# 07-KSZ9031_1G_BASET_XCVR.net
KiCad netlist of a schematic drawn in Altium Designer
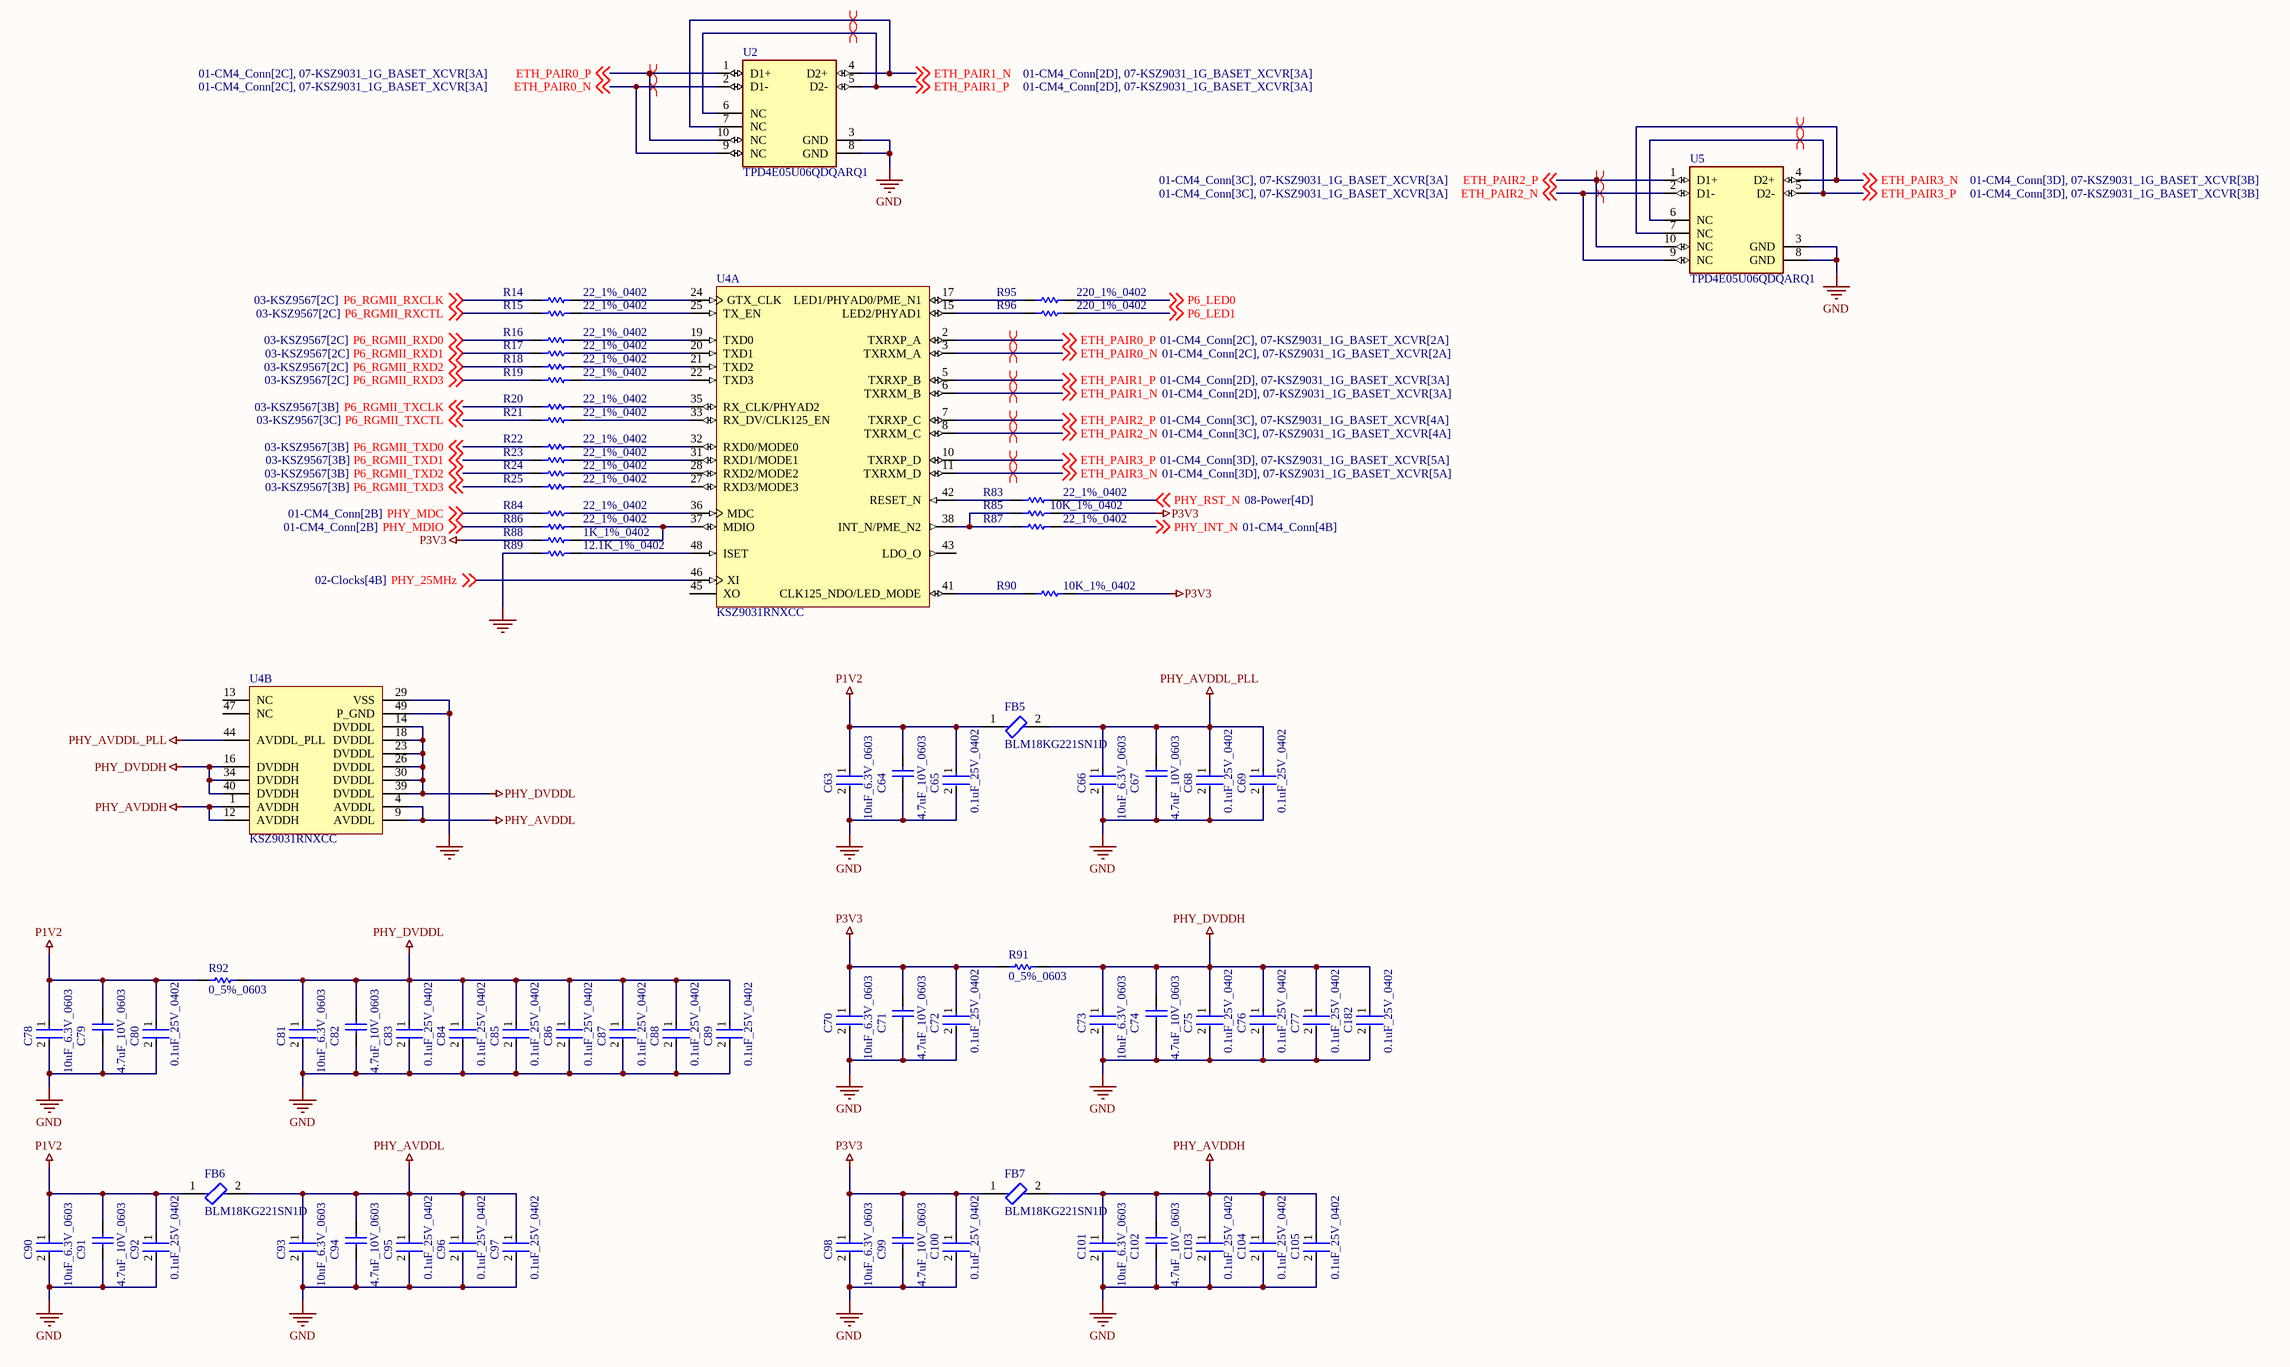
[diagram p0: 07-KSZ9031_1G_BASET_XCVR.SchDoc]

(export (version "E")
  (design (tool "Eeschema 10.0.6"))
  (components
    (comp (ref "C63")
      (value "10uF_6.3V_0603")
      (footprint "FP-C0603C106M9PACTU-MFG")
      (description "CAP CER 10UF 6.3V X5R 0603")
      (fields
        (field (name "MANUFACTURER PART NUMBER") "C0603C106M9PACTU")
        (field (name "MANUFACTURER") "Kemet")
      )
      (libsource (lib "Altium Content Vault") (part "b4654b650e69147ec39a6b967a45e02"))
    )
    (comp (ref "C64")
      (value "4.7uF_10V_0603")
      (footprint "CAPC1608X87X35NL15T15")
      (fields (field (name "PART NUMBER") "C0603C475K8PACTU") (field (name "MANUFACTURER") "Kemet"))
      (libsource (lib "Altium Content Vault") (part "CAP"))
    )
    (comp (ref "C65")
      (value "0.1uF_25V_0402")
      (footprint "FP-0402-L_1_0_1-W_0_5_0_1-IPC_C")
      (description "General Purpose Ceramic Capacitor, 0402, 100nF, 10%, X7R, 15%, 25V")
      (fields (field (name "VOLTAGE") "25V") (field (name "TOLERANCE") "10%"))
      (libsource (lib "Altium Content Vault") (part "b4654b650e69147ec39a6b967a45e02"))
    )
    (comp (ref "C66")
      (value "10uF_6.3V_0603")
      (footprint "FP-C0603C106M9PACTU-MFG")
      (description "CAP CER 10UF 6.3V X5R 0603")
      (fields
        (field (name "MANUFACTURER PART NUMBER") "C0603C106M9PACTU")
        (field (name "MANUFACTURER") "Kemet")
      )
      (libsource (lib "Altium Content Vault") (part "b4654b650e69147ec39a6b967a45e02"))
    )
    (comp (ref "C67")
      (value "4.7uF_10V_0603")
      (footprint "CAPC1608X87X35NL15T15")
      (fields (field (name "PART NUMBER") "C0603C475K8PACTU") (field (name "MANUFACTURER") "Kemet"))
      (libsource (lib "Altium Content Vault") (part "CAP"))
    )
    (comp (ref "C68")
      (value "0.1uF_25V_0402")
      (footprint "FP-0402-L_1_0_1-W_0_5_0_1-IPC_C")
      (description "General Purpose Ceramic Capacitor, 0402, 100nF, 10%, X7R, 15%, 25V")
      (fields (field (name "VOLTAGE") "25V") (field (name "TOLERANCE") "10%"))
      (libsource (lib "Altium Content Vault") (part "b4654b650e69147ec39a6b967a45e02"))
    )
    (comp (ref "C69")
      (value "0.1uF_25V_0402")
      (footprint "FP-0402-L_1_0_1-W_0_5_0_1-IPC_C")
      (description "General Purpose Ceramic Capacitor, 0402, 100nF, 10%, X7R, 15%, 25V")
      (fields (field (name "VOLTAGE") "25V") (field (name "TOLERANCE") "10%"))
      (libsource (lib "Altium Content Vault") (part "b4654b650e69147ec39a6b967a45e02"))
    )
    (comp (ref "C70")
      (value "10uF_6.3V_0603")
      (footprint "FP-C0603C106M9PACTU-MFG")
      (description "CAP CER 10UF 6.3V X5R 0603")
      (fields
        (field (name "MANUFACTURER PART NUMBER") "C0603C106M9PACTU")
        (field (name "MANUFACTURER") "Kemet")
      )
      (libsource (lib "Altium Content Vault") (part "b4654b650e69147ec39a6b967a45e02"))
    )
    (comp (ref "C71")
      (value "4.7uF_10V_0603")
      (footprint "CAPC1608X87X35NL15T15")
      (fields (field (name "PART NUMBER") "C0603C475K8PACTU") (field (name "MANUFACTURER") "Kemet"))
      (libsource (lib "Altium Content Vault") (part "CAP"))
    )
    (comp (ref "C72")
      (value "0.1uF_25V_0402")
      (footprint "FP-0402-L_1_0_1-W_0_5_0_1-IPC_C")
      (description "General Purpose Ceramic Capacitor, 0402, 100nF, 10%, X7R, 15%, 25V")
      (fields (field (name "VOLTAGE") "25V") (field (name "TOLERANCE") "10%"))
      (libsource (lib "Altium Content Vault") (part "b4654b650e69147ec39a6b967a45e02"))
    )
    (comp (ref "C73")
      (value "10uF_6.3V_0603")
      (footprint "FP-C0603C106M9PACTU-MFG")
      (description "CAP CER 10UF 6.3V X5R 0603")
      (fields
        (field (name "MANUFACTURER PART NUMBER") "C0603C106M9PACTU")
        (field (name "MANUFACTURER") "Kemet")
      )
      (libsource (lib "Altium Content Vault") (part "b4654b650e69147ec39a6b967a45e02"))
    )
    (comp (ref "C74")
      (value "4.7uF_10V_0603")
      (footprint "CAPC1608X87X35NL15T15")
      (fields (field (name "PART NUMBER") "C0603C475K8PACTU") (field (name "MANUFACTURER") "Kemet"))
      (libsource (lib "Altium Content Vault") (part "CAP"))
    )
    (comp (ref "C75")
      (value "0.1uF_25V_0402")
      (footprint "FP-0402-L_1_0_1-W_0_5_0_1-IPC_C")
      (description "General Purpose Ceramic Capacitor, 0402, 100nF, 10%, X7R, 15%, 25V")
      (fields (field (name "VOLTAGE") "25V") (field (name "TOLERANCE") "10%"))
      (libsource (lib "Altium Content Vault") (part "b4654b650e69147ec39a6b967a45e02"))
    )
    (comp (ref "C76")
      (value "0.1uF_25V_0402")
      (footprint "FP-0402-L_1_0_1-W_0_5_0_1-IPC_C")
      (description "General Purpose Ceramic Capacitor, 0402, 100nF, 10%, X7R, 15%, 25V")
      (fields (field (name "VOLTAGE") "25V") (field (name "TOLERANCE") "10%"))
      (libsource (lib "Altium Content Vault") (part "b4654b650e69147ec39a6b967a45e02"))
    )
    (comp (ref "C77")
      (value "0.1uF_25V_0402")
      (footprint "FP-0402-L_1_0_1-W_0_5_0_1-IPC_C")
      (description "General Purpose Ceramic Capacitor, 0402, 100nF, 10%, X7R, 15%, 25V")
      (fields (field (name "VOLTAGE") "25V") (field (name "TOLERANCE") "10%"))
      (libsource (lib "Altium Content Vault") (part "b4654b650e69147ec39a6b967a45e02"))
    )
    (comp (ref "C78")
      (value "10uF_6.3V_0603")
      (footprint "FP-C0603C106M9PACTU-MFG")
      (description "CAP CER 10UF 6.3V X5R 0603")
      (fields
        (field (name "MANUFACTURER PART NUMBER") "C0603C106M9PACTU")
        (field (name "MANUFACTURER") "Kemet")
      )
      (libsource (lib "Altium Content Vault") (part "b4654b650e69147ec39a6b967a45e02"))
    )
    (comp (ref "C79")
      (value "4.7uF_10V_0603")
      (footprint "CAPC1608X87X35NL15T15")
      (fields (field (name "PART NUMBER") "C0603C475K8PACTU") (field (name "MANUFACTURER") "Kemet"))
      (libsource (lib "Altium Content Vault") (part "CAP"))
    )
    (comp (ref "C80")
      (value "0.1uF_25V_0402")
      (footprint "FP-0402-L_1_0_1-W_0_5_0_1-IPC_C")
      (description "General Purpose Ceramic Capacitor, 0402, 100nF, 10%, X7R, 15%, 25V")
      (fields (field (name "VOLTAGE") "25V") (field (name "TOLERANCE") "10%"))
      (libsource (lib "Altium Content Vault") (part "b4654b650e69147ec39a6b967a45e02"))
    )
    (comp (ref "C81")
      (value "10uF_6.3V_0603")
      (footprint "FP-C0603C106M9PACTU-MFG")
      (description "CAP CER 10UF 6.3V X5R 0603")
      (fields
        (field (name "MANUFACTURER PART NUMBER") "C0603C106M9PACTU")
        (field (name "MANUFACTURER") "Kemet")
      )
      (libsource (lib "Altium Content Vault") (part "b4654b650e69147ec39a6b967a45e02"))
    )
    (comp (ref "C82")
      (value "4.7uF_10V_0603")
      (footprint "CAPC1608X87X35NL15T15")
      (fields (field (name "PART NUMBER") "C0603C475K8PACTU") (field (name "MANUFACTURER") "Kemet"))
      (libsource (lib "Altium Content Vault") (part "CAP"))
    )
    (comp (ref "C83")
      (value "0.1uF_25V_0402")
      (footprint "FP-0402-L_1_0_1-W_0_5_0_1-IPC_C")
      (description "General Purpose Ceramic Capacitor, 0402, 100nF, 10%, X7R, 15%, 25V")
      (fields (field (name "VOLTAGE") "25V") (field (name "TOLERANCE") "10%"))
      (libsource (lib "Altium Content Vault") (part "b4654b650e69147ec39a6b967a45e02"))
    )
    (comp (ref "C84")
      (value "0.1uF_25V_0402")
      (footprint "FP-0402-L_1_0_1-W_0_5_0_1-IPC_C")
      (description "General Purpose Ceramic Capacitor, 0402, 100nF, 10%, X7R, 15%, 25V")
      (fields (field (name "VOLTAGE") "25V") (field (name "TOLERANCE") "10%"))
      (libsource (lib "Altium Content Vault") (part "b4654b650e69147ec39a6b967a45e02"))
    )
    (comp (ref "C85")
      (value "0.1uF_25V_0402")
      (footprint "FP-0402-L_1_0_1-W_0_5_0_1-IPC_C")
      (description "General Purpose Ceramic Capacitor, 0402, 100nF, 10%, X7R, 15%, 25V")
      (fields (field (name "VOLTAGE") "25V") (field (name "TOLERANCE") "10%"))
      (libsource (lib "Altium Content Vault") (part "b4654b650e69147ec39a6b967a45e02"))
    )
    (comp (ref "C86")
      (value "0.1uF_25V_0402")
      (footprint "FP-0402-L_1_0_1-W_0_5_0_1-IPC_C")
      (description "General Purpose Ceramic Capacitor, 0402, 100nF, 10%, X7R, 15%, 25V")
      (fields (field (name "VOLTAGE") "25V") (field (name "TOLERANCE") "10%"))
      (libsource (lib "Altium Content Vault") (part "b4654b650e69147ec39a6b967a45e02"))
    )
    (comp (ref "C87")
      (value "0.1uF_25V_0402")
      (footprint "FP-0402-L_1_0_1-W_0_5_0_1-IPC_C")
      (description "General Purpose Ceramic Capacitor, 0402, 100nF, 10%, X7R, 15%, 25V")
      (fields (field (name "VOLTAGE") "25V") (field (name "TOLERANCE") "10%"))
      (libsource (lib "Altium Content Vault") (part "b4654b650e69147ec39a6b967a45e02"))
    )
    (comp (ref "C88")
      (value "0.1uF_25V_0402")
      (footprint "FP-0402-L_1_0_1-W_0_5_0_1-IPC_C")
      (description "General Purpose Ceramic Capacitor, 0402, 100nF, 10%, X7R, 15%, 25V")
      (fields (field (name "VOLTAGE") "25V") (field (name "TOLERANCE") "10%"))
      (libsource (lib "Altium Content Vault") (part "b4654b650e69147ec39a6b967a45e02"))
    )
    (comp (ref "C89")
      (value "0.1uF_25V_0402")
      (footprint "FP-0402-L_1_0_1-W_0_5_0_1-IPC_C")
      (description "General Purpose Ceramic Capacitor, 0402, 100nF, 10%, X7R, 15%, 25V")
      (fields (field (name "VOLTAGE") "25V") (field (name "TOLERANCE") "10%"))
      (libsource (lib "Altium Content Vault") (part "b4654b650e69147ec39a6b967a45e02"))
    )
    (comp (ref "C90")
      (value "10uF_6.3V_0603")
      (footprint "FP-C0603C106M9PACTU-MFG")
      (description "CAP CER 10UF 6.3V X5R 0603")
      (fields
        (field (name "MANUFACTURER PART NUMBER") "C0603C106M9PACTU")
        (field (name "MANUFACTURER") "Kemet")
      )
      (libsource (lib "Altium Content Vault") (part "b4654b650e69147ec39a6b967a45e02"))
    )
    (comp (ref "C91")
      (value "4.7uF_10V_0603")
      (footprint "CAPC1608X87X35NL15T15")
      (fields (field (name "PART NUMBER") "C0603C475K8PACTU") (field (name "MANUFACTURER") "Kemet"))
      (libsource (lib "Altium Content Vault") (part "CAP"))
    )
    (comp (ref "C92")
      (value "0.1uF_25V_0402")
      (footprint "FP-0402-L_1_0_1-W_0_5_0_1-IPC_C")
      (description "General Purpose Ceramic Capacitor, 0402, 100nF, 10%, X7R, 15%, 25V")
      (fields (field (name "VOLTAGE") "25V") (field (name "TOLERANCE") "10%"))
      (libsource (lib "Altium Content Vault") (part "b4654b650e69147ec39a6b967a45e02"))
    )
    (comp (ref "C93")
      (value "10uF_6.3V_0603")
      (footprint "FP-C0603C106M9PACTU-MFG")
      (description "CAP CER 10UF 6.3V X5R 0603")
      (fields
        (field (name "MANUFACTURER PART NUMBER") "C0603C106M9PACTU")
        (field (name "MANUFACTURER") "Kemet")
      )
      (libsource (lib "Altium Content Vault") (part "b4654b650e69147ec39a6b967a45e02"))
    )
    (comp (ref "C94")
      (value "4.7uF_10V_0603")
      (footprint "CAPC1608X87X35NL15T15")
      (fields (field (name "PART NUMBER") "C0603C475K8PACTU") (field (name "MANUFACTURER") "Kemet"))
      (libsource (lib "Altium Content Vault") (part "CAP"))
    )
    (comp (ref "C95")
      (value "0.1uF_25V_0402")
      (footprint "FP-0402-L_1_0_1-W_0_5_0_1-IPC_C")
      (description "General Purpose Ceramic Capacitor, 0402, 100nF, 10%, X7R, 15%, 25V")
      (fields (field (name "VOLTAGE") "25V") (field (name "TOLERANCE") "10%"))
      (libsource (lib "Altium Content Vault") (part "b4654b650e69147ec39a6b967a45e02"))
    )
    (comp (ref "C96")
      (value "0.1uF_25V_0402")
      (footprint "FP-0402-L_1_0_1-W_0_5_0_1-IPC_C")
      (description "General Purpose Ceramic Capacitor, 0402, 100nF, 10%, X7R, 15%, 25V")
      (fields (field (name "VOLTAGE") "25V") (field (name "TOLERANCE") "10%"))
      (libsource (lib "Altium Content Vault") (part "b4654b650e69147ec39a6b967a45e02"))
    )
    (comp (ref "C97")
      (value "0.1uF_25V_0402")
      (footprint "FP-0402-L_1_0_1-W_0_5_0_1-IPC_C")
      (description "General Purpose Ceramic Capacitor, 0402, 100nF, 10%, X7R, 15%, 25V")
      (fields (field (name "VOLTAGE") "25V") (field (name "TOLERANCE") "10%"))
      (libsource (lib "Altium Content Vault") (part "b4654b650e69147ec39a6b967a45e02"))
    )
    (comp (ref "C98")
      (value "10uF_6.3V_0603")
      (footprint "FP-C0603C106M9PACTU-MFG")
      (description "CAP CER 10UF 6.3V X5R 0603")
      (fields
        (field (name "MANUFACTURER PART NUMBER") "C0603C106M9PACTU")
        (field (name "MANUFACTURER") "Kemet")
      )
      (libsource (lib "Altium Content Vault") (part "b4654b650e69147ec39a6b967a45e02"))
    )
    (comp (ref "C99")
      (value "4.7uF_10V_0603")
      (footprint "CAPC1608X87X35NL15T15")
      (fields (field (name "PART NUMBER") "C0603C475K8PACTU") (field (name "MANUFACTURER") "Kemet"))
      (libsource (lib "Altium Content Vault") (part "CAP"))
    )
    (comp (ref "C100")
      (value "0.1uF_25V_0402")
      (footprint "FP-0402-L_1_0_1-W_0_5_0_1-IPC_C")
      (description "General Purpose Ceramic Capacitor, 0402, 100nF, 10%, X7R, 15%, 25V")
      (fields (field (name "VOLTAGE") "25V") (field (name "TOLERANCE") "10%"))
      (libsource (lib "Altium Content Vault") (part "b4654b650e69147ec39a6b967a45e02"))
    )
    (comp (ref "C101")
      (value "10uF_6.3V_0603")
      (footprint "FP-C0603C106M9PACTU-MFG")
      (description "CAP CER 10UF 6.3V X5R 0603")
      (fields
        (field (name "MANUFACTURER PART NUMBER") "C0603C106M9PACTU")
        (field (name "MANUFACTURER") "Kemet")
      )
      (libsource (lib "Altium Content Vault") (part "b4654b650e69147ec39a6b967a45e02"))
    )
    (comp (ref "C102")
      (value "4.7uF_10V_0603")
      (footprint "CAPC1608X87X35NL15T15")
      (fields (field (name "PART NUMBER") "C0603C475K8PACTU") (field (name "MANUFACTURER") "Kemet"))
      (libsource (lib "Altium Content Vault") (part "CAP"))
    )
    (comp (ref "C103")
      (value "0.1uF_25V_0402")
      (footprint "FP-0402-L_1_0_1-W_0_5_0_1-IPC_C")
      (description "General Purpose Ceramic Capacitor, 0402, 100nF, 10%, X7R, 15%, 25V")
      (fields (field (name "VOLTAGE") "25V") (field (name "TOLERANCE") "10%"))
      (libsource (lib "Altium Content Vault") (part "b4654b650e69147ec39a6b967a45e02"))
    )
    (comp (ref "C104")
      (value "0.1uF_25V_0402")
      (footprint "FP-0402-L_1_0_1-W_0_5_0_1-IPC_C")
      (description "General Purpose Ceramic Capacitor, 0402, 100nF, 10%, X7R, 15%, 25V")
      (fields (field (name "VOLTAGE") "25V") (field (name "TOLERANCE") "10%"))
      (libsource (lib "Altium Content Vault") (part "b4654b650e69147ec39a6b967a45e02"))
    )
    (comp (ref "C105")
      (value "0.1uF_25V_0402")
      (footprint "FP-0402-L_1_0_1-W_0_5_0_1-IPC_C")
      (description "General Purpose Ceramic Capacitor, 0402, 100nF, 10%, X7R, 15%, 25V")
      (fields (field (name "VOLTAGE") "25V") (field (name "TOLERANCE") "10%"))
      (libsource (lib "Altium Content Vault") (part "b4654b650e69147ec39a6b967a45e02"))
    )
    (comp (ref "C182")
      (value "0.1uF_25V_0402")
      (footprint "FP-0402-L_1_0_1-W_0_5_0_1-IPC_C")
      (description "General Purpose Ceramic Capacitor, 0402, 100nF, 10%, X7R, 15%, 25V")
      (fields (field (name "VOLTAGE") "25V") (field (name "TOLERANCE") "10%"))
      (libsource (lib "Altium Content Vault") (part "b4654b650e69147ec39a6b967a45e02"))
    )
    (comp (ref "FB5")
      (value "BLM18KG221SN1D")
      (footprint "FP-BLM18-0_15-t0_8-IPC_B")
      (description "Chip Ferrite Bead, 0603, 220Ω @ 100MHz, 0.05Ω, 25%, 2.2A")
      (fields (field (name "TOLERANCE") "25%"))
      (libsource (lib "Altium Content Vault") (part "5f30dd21d616792df468990f7003faa"))
    )
    (comp (ref "FB6")
      (value "BLM18KG221SN1D")
      (footprint "FP-BLM18-0_15-t0_8-IPC_B")
      (description "Chip Ferrite Bead, 0603, 220Ω @ 100MHz, 0.05Ω, 25%, 2.2A")
      (fields (field (name "TOLERANCE") "25%"))
      (libsource (lib "Altium Content Vault") (part "5f30dd21d616792df468990f7003faa"))
    )
    (comp (ref "FB7")
      (value "BLM18KG221SN1D")
      (footprint "FP-BLM18-0_15-t0_8-IPC_B")
      (description "Chip Ferrite Bead, 0603, 220Ω @ 100MHz, 0.05Ω, 25%, 2.2A")
      (fields (field (name "TOLERANCE") "25%"))
      (libsource (lib "Altium Content Vault") (part "5f30dd21d616792df468990f7003faa"))
    )
    (comp (ref "R14")
      (value "22_1%_0402")
      (footprint "RESC1005X40X25ML05T10")
      (fields (field (name "PART NUMBER") "RC0402FR-1322RL") (field (name "MANUFACTURER") "Yageo / Phycomp"))
      (libsource (lib "Altium Content Vault") (part "RES"))
    )
    (comp (ref "R15")
      (value "22_1%_0402")
      (footprint "RESC1005X40X25ML05T10")
      (fields (field (name "PART NUMBER") "RC0402FR-1322RL") (field (name "MANUFACTURER") "Yageo / Phycomp"))
      (libsource (lib "Altium Content Vault") (part "RES"))
    )
    (comp (ref "R16")
      (value "22_1%_0402")
      (footprint "RESC1005X40X25ML05T10")
      (fields (field (name "PART NUMBER") "RC0402FR-1322RL") (field (name "MANUFACTURER") "Yageo / Phycomp"))
      (libsource (lib "Altium Content Vault") (part "RES"))
    )
    (comp (ref "R17")
      (value "22_1%_0402")
      (footprint "RESC1005X40X25ML05T10")
      (fields (field (name "PART NUMBER") "RC0402FR-1322RL") (field (name "MANUFACTURER") "Yageo / Phycomp"))
      (libsource (lib "Altium Content Vault") (part "RES"))
    )
    (comp (ref "R18")
      (value "22_1%_0402")
      (footprint "RESC1005X40X25ML05T10")
      (fields (field (name "PART NUMBER") "RC0402FR-1322RL") (field (name "MANUFACTURER") "Yageo / Phycomp"))
      (libsource (lib "Altium Content Vault") (part "RES"))
    )
    (comp (ref "R19")
      (value "22_1%_0402")
      (footprint "RESC1005X40X25ML05T10")
      (fields (field (name "PART NUMBER") "RC0402FR-1322RL") (field (name "MANUFACTURER") "Yageo / Phycomp"))
      (libsource (lib "Altium Content Vault") (part "RES"))
    )
    (comp (ref "R20")
      (value "22_1%_0402")
      (footprint "RESC1005X40X25ML05T10")
      (fields (field (name "PART NUMBER") "RC0402FR-1322RL") (field (name "MANUFACTURER") "Yageo / Phycomp"))
      (libsource (lib "Altium Content Vault") (part "RES"))
    )
    (comp (ref "R21")
      (value "22_1%_0402")
      (footprint "RESC1005X40X25ML05T10")
      (fields (field (name "PART NUMBER") "RC0402FR-1322RL") (field (name "MANUFACTURER") "Yageo / Phycomp"))
      (libsource (lib "Altium Content Vault") (part "RES"))
    )
    (comp (ref "R22")
      (value "22_1%_0402")
      (footprint "RESC1005X40X25ML05T10")
      (fields (field (name "PART NUMBER") "RC0402FR-1322RL") (field (name "MANUFACTURER") "Yageo / Phycomp"))
      (libsource (lib "Altium Content Vault") (part "RES"))
    )
    (comp (ref "R23")
      (value "22_1%_0402")
      (footprint "RESC1005X40X25ML05T10")
      (fields (field (name "PART NUMBER") "RC0402FR-1322RL") (field (name "MANUFACTURER") "Yageo / Phycomp"))
      (libsource (lib "Altium Content Vault") (part "RES"))
    )
    (comp (ref "R24")
      (value "22_1%_0402")
      (footprint "RESC1005X40X25ML05T10")
      (fields (field (name "PART NUMBER") "RC0402FR-1322RL") (field (name "MANUFACTURER") "Yageo / Phycomp"))
      (libsource (lib "Altium Content Vault") (part "RES"))
    )
    (comp (ref "R25")
      (value "22_1%_0402")
      (footprint "RESC1005X40X25ML05T10")
      (fields (field (name "PART NUMBER") "RC0402FR-1322RL") (field (name "MANUFACTURER") "Yageo / Phycomp"))
      (libsource (lib "Altium Content Vault") (part "RES"))
    )
    (comp (ref "R83")
      (value "22_1%_0402")
      (footprint "RESC1005X40X25ML05T10")
      (fields (field (name "PART NUMBER") "RC0402FR-1322RL") (field (name "MANUFACTURER") "Yageo / Phycomp"))
      (libsource (lib "Altium Content Vault") (part "RES"))
    )
    (comp (ref "R84")
      (value "22_1%_0402")
      (footprint "RESC1005X40X25ML05T10")
      (fields (field (name "PART NUMBER") "RC0402FR-1322RL") (field (name "MANUFACTURER") "Yageo / Phycomp"))
      (libsource (lib "Altium Content Vault") (part "RES"))
    )
    (comp (ref "R85")
      (value "10K_1%_0402")
      (footprint "RESC1005X40X25NL10T10")
      (fields (field (name "MANUFACTURER") "Bourns") (field (name "PART NUMBER") "CR0402-FX-1002GLF"))
      (libsource (lib "Altium Content Vault") (part "RES"))
    )
    (comp (ref "R86")
      (value "22_1%_0402")
      (footprint "RESC1005X40X25ML05T10")
      (fields (field (name "PART NUMBER") "RC0402FR-1322RL") (field (name "MANUFACTURER") "Yageo / Phycomp"))
      (libsource (lib "Altium Content Vault") (part "RES"))
    )
    (comp (ref "R87")
      (value "22_1%_0402")
      (footprint "RESC1005X40X25ML05T10")
      (fields (field (name "PART NUMBER") "RC0402FR-1322RL") (field (name "MANUFACTURER") "Yageo / Phycomp"))
      (libsource (lib "Altium Content Vault") (part "RES"))
    )
    (comp (ref "R88")
      (value "1K_1%_0402")
      (footprint "RESC1005X40X25ML05T10")
      (fields (field (name "MANUFACTURER") "Multicomp") (field (name "PART NUMBER") "MCMR04X1001FTL"))
      (libsource (lib "Altium Content Vault") (part "RES"))
    )
    (comp (ref "R89")
      (value "12.1K_1%_0402")
      (footprint "RESC1005X40X25NL10T10")
      (fields (field (name "MANUFACTURER") "Multicomp") (field (name "PART NUMBER") "MC00625W0402112K1"))
      (libsource (lib "Altium Content Vault") (part "RES"))
    )
    (comp (ref "R90")
      (value "10K_1%_0402")
      (footprint "RESC1005X40X25NL10T10")
      (fields (field (name "MANUFACTURER") "Bourns") (field (name "PART NUMBER") "CR0402-FX-1002GLF"))
      (libsource (lib "Altium Content Vault") (part "RES"))
    )
    (comp (ref "R91")
      (value "0_5%_0603")
      (footprint "RESC1608X55X25ML10T15")
      (description "Chip Resistor, 0 Ohm, +/- 5%, 0.1 W, -55 to 155 degC, 0603 (1608 Metric), RoHS, Tape and Reel")
      (fields (field (name "TOLERANCE") "5%") (field (name "MANUFACTURER") "Yageo"))
      (libsource (lib "Altium Content Vault") (part "RES-2"))
    )
    (comp (ref "R92")
      (value "0_5%_0603")
      (footprint "RESC1608X55X25ML10T15")
      (description "Chip Resistor, 0 Ohm, +/- 5%, 0.1 W, -55 to 155 degC, 0603 (1608 Metric), RoHS, Tape and Reel")
      (fields (field (name "TOLERANCE") "5%") (field (name "MANUFACTURER") "Yageo"))
      (libsource (lib "Altium Content Vault") (part "RES-2"))
    )
    (comp (ref "R95")
      (value "220_1%_0402")
      (footprint "RESC1005X40X25NL05T10")
      (fields (field (name "MANUFACTURER") "Yageo / Phycomp") (field (name "PART NUMBER") "RC0402JR-07220RL"))
      (libsource (lib "Altium Content Vault") (part "RES"))
    )
    (comp (ref "R96")
      (value "220_1%_0402")
      (footprint "RESC1005X40X25NL05T10")
      (fields (field (name "MANUFACTURER") "Yageo / Phycomp") (field (name "PART NUMBER") "RC0402JR-07220RL"))
      (libsource (lib "Altium Content Vault") (part "RES"))
    )
    (comp (ref "U2")
      (value "TPD4E05U06QDQARQ1")
      (footprint "FP-DQA0010A-MFG")
      (description "TVS DIODE 5.5V 14V 10USON")
      (fields
        (field (name "OCTOPART") "https://octopart.com/tpd4e05u06qdqarq1-texas+instruments-48523459")
        (field (name "MANUFACTURER") "Texas Instruments")
      )
      (libsource (lib "Altium Content Vault") (part "f11f7ff102fa2b028e1355c732c836d"))
    )
    (comp (ref "U4")
      (value "KSZ9031RNXCC")
      (footprint "MICL-QFN-48_V")
      (description "Gigabit Ethernet Transceiver with RGMII Support, 1.14 to 1.26 V, 0 to 70 degC, 48-Pin QFN, RoHS")
      (fields (field (name "MANUFACTURER") "Micrel"))
      (libsource (lib "Altium Content Vault") (part "MICL-KSZ9031RNX-48"))
    )
    (comp (ref "U5")
      (value "TPD4E05U06QDQARQ1")
      (footprint "FP-DQA0010A-MFG")
      (description "TVS DIODE 5.5V 14V 10USON")
      (fields
        (field (name "OCTOPART") "https://octopart.com/tpd4e05u06qdqarq1-texas+instruments-48523459")
        (field (name "MANUFACTURER") "Texas Instruments")
      )
      (libsource (lib "Altium Content Vault") (part "f11f7ff102fa2b028e1355c732c836d"))
    )
  )
  (nets
    (net (code "1") (name "ETH_PAIR0_N") (class "Default")
      (node (ref "U2") (pin "2") (pinfunction "D1-_2") (pintype "bidirectional"))
      (node (ref "U2") (pin "9") (pinfunction "NC_9") (pintype "bidirectional"))
      (node (ref "U4") (pin "3") (pinfunction "TXRXM_A_3") (pintype "bidirectional"))
    )
    (net (code "2") (name "ETH_PAIR0_P") (class "Default")
      (node (ref "U2") (pin "1") (pinfunction "D1+_1") (pintype "bidirectional"))
      (node (ref "U2") (pin "10") (pinfunction "NC_10") (pintype "bidirectional"))
      (node (ref "U4") (pin "2") (pinfunction "TXRXP_A_2") (pintype "bidirectional"))
    )
    (net (code "3") (name "ETH_PAIR1_N") (class "Default")
      (node (ref "U2") (pin "4") (pinfunction "D2+_4") (pintype "bidirectional"))
      (node (ref "U2") (pin "7") (pinfunction "NC_7") (pintype "passive"))
      (node (ref "U4") (pin "6") (pinfunction "TXRXM_B_6") (pintype "bidirectional"))
    )
    (net (code "4") (name "ETH_PAIR1_P") (class "Default")
      (node (ref "U2") (pin "5") (pinfunction "D2-_5") (pintype "bidirectional"))
      (node (ref "U2") (pin "6") (pinfunction "NC_6") (pintype "passive"))
      (node (ref "U4") (pin "5") (pinfunction "TXRXP_B_5") (pintype "bidirectional"))
    )
    (net (code "5") (name "ETH_PAIR2_N") (class "Default")
      (node (ref "U4") (pin "8") (pinfunction "TXRXM_C_8") (pintype "bidirectional"))
      (node (ref "U5") (pin "2") (pinfunction "D1-_2") (pintype "bidirectional"))
      (node (ref "U5") (pin "9") (pinfunction "NC_9") (pintype "bidirectional"))
    )
    (net (code "6") (name "ETH_PAIR2_P") (class "Default")
      (node (ref "U4") (pin "7") (pinfunction "TXRXP_C_7") (pintype "bidirectional"))
      (node (ref "U5") (pin "1") (pinfunction "D1+_1") (pintype "bidirectional"))
      (node (ref "U5") (pin "10") (pinfunction "NC_10") (pintype "bidirectional"))
    )
    (net (code "7") (name "ETH_PAIR3_N") (class "Default")
      (node (ref "U4") (pin "11") (pinfunction "TXRXM_D_11") (pintype "bidirectional"))
      (node (ref "U5") (pin "4") (pinfunction "D2+_4") (pintype "bidirectional"))
      (node (ref "U5") (pin "7") (pinfunction "NC_7") (pintype "passive"))
    )
    (net (code "8") (name "ETH_PAIR3_P") (class "Default")
      (node (ref "U4") (pin "10") (pinfunction "TXRXP_D_10") (pintype "bidirectional"))
      (node (ref "U5") (pin "5") (pinfunction "D2-_5") (pintype "bidirectional"))
      (node (ref "U5") (pin "6") (pinfunction "NC_6") (pintype "passive"))
    )
    (net (code "9") (name "GND") (class "Default")
      (node (ref "C100") (pin "2") (pinfunction "2_2") (pintype "passive"))
      (node (ref "C101") (pin "2") (pinfunction "2_2") (pintype "passive"))
      (node (ref "C102") (pin "1") (pinfunction "1_1") (pintype "passive"))
      (node (ref "C103") (pin "2") (pinfunction "2_2") (pintype "passive"))
      (node (ref "C104") (pin "2") (pinfunction "2_2") (pintype "passive"))
      (node (ref "C105") (pin "2") (pinfunction "2_2") (pintype "passive"))
      (node (ref "C182") (pin "2") (pinfunction "2_2") (pintype "passive"))
      (node (ref "C63") (pin "2") (pinfunction "2_2") (pintype "passive"))
      (node (ref "C64") (pin "1") (pinfunction "1_1") (pintype "passive"))
      (node (ref "C65") (pin "2") (pinfunction "2_2") (pintype "passive"))
      (node (ref "C66") (pin "2") (pinfunction "2_2") (pintype "passive"))
      (node (ref "C67") (pin "1") (pinfunction "1_1") (pintype "passive"))
      (node (ref "C68") (pin "2") (pinfunction "2_2") (pintype "passive"))
      (node (ref "C69") (pin "2") (pinfunction "2_2") (pintype "passive"))
      (node (ref "C70") (pin "2") (pinfunction "2_2") (pintype "passive"))
      (node (ref "C71") (pin "1") (pinfunction "1_1") (pintype "passive"))
      (node (ref "C72") (pin "2") (pinfunction "2_2") (pintype "passive"))
      (node (ref "C73") (pin "2") (pinfunction "2_2") (pintype "passive"))
      (node (ref "C74") (pin "1") (pinfunction "1_1") (pintype "passive"))
      (node (ref "C75") (pin "2") (pinfunction "2_2") (pintype "passive"))
      (node (ref "C76") (pin "2") (pinfunction "2_2") (pintype "passive"))
      (node (ref "C77") (pin "2") (pinfunction "2_2") (pintype "passive"))
      (node (ref "C78") (pin "2") (pinfunction "2_2") (pintype "passive"))
      (node (ref "C79") (pin "1") (pinfunction "1_1") (pintype "passive"))
      (node (ref "C80") (pin "2") (pinfunction "2_2") (pintype "passive"))
      (node (ref "C81") (pin "2") (pinfunction "2_2") (pintype "passive"))
      (node (ref "C82") (pin "1") (pinfunction "1_1") (pintype "passive"))
      (node (ref "C83") (pin "2") (pinfunction "2_2") (pintype "passive"))
      (node (ref "C84") (pin "2") (pinfunction "2_2") (pintype "passive"))
      (node (ref "C85") (pin "2") (pinfunction "2_2") (pintype "passive"))
      (node (ref "C86") (pin "2") (pinfunction "2_2") (pintype "passive"))
      (node (ref "C87") (pin "2") (pinfunction "2_2") (pintype "passive"))
      (node (ref "C88") (pin "2") (pinfunction "2_2") (pintype "passive"))
      (node (ref "C89") (pin "2") (pinfunction "2_2") (pintype "passive"))
      (node (ref "C90") (pin "2") (pinfunction "2_2") (pintype "passive"))
      (node (ref "C91") (pin "1") (pinfunction "1_1") (pintype "passive"))
      (node (ref "C92") (pin "2") (pinfunction "2_2") (pintype "passive"))
      (node (ref "C93") (pin "2") (pinfunction "2_2") (pintype "passive"))
      (node (ref "C94") (pin "1") (pinfunction "1_1") (pintype "passive"))
      (node (ref "C95") (pin "2") (pinfunction "2_2") (pintype "passive"))
      (node (ref "C96") (pin "2") (pinfunction "2_2") (pintype "passive"))
      (node (ref "C97") (pin "2") (pinfunction "2_2") (pintype "passive"))
      (node (ref "C98") (pin "2") (pinfunction "2_2") (pintype "passive"))
      (node (ref "C99") (pin "1") (pinfunction "1_1") (pintype "passive"))
      (node (ref "R89") (pin "1") (pinfunction "1_1") (pintype "passive"))
      (node (ref "U2") (pin "3") (pinfunction "GND_3") (pintype "power_in"))
      (node (ref "U2") (pin "8") (pinfunction "GND_8") (pintype "power_in"))
      (node (ref "U4") (pin "29") (pinfunction "VSS_29") (pintype "power_in"))
      (node (ref "U4") (pin "49") (pinfunction "P_GND_49") (pintype "power_in"))
      (node (ref "U5") (pin "3") (pinfunction "GND_3") (pintype "power_in"))
      (node (ref "U5") (pin "8") (pinfunction "GND_8") (pintype "power_in"))
    )
    (net (code "10") (name "Net-(U4A-CLK125_NDO{slash}LED_MODE)") (class "Default")
      (node (ref "R90") (pin "1") (pinfunction "1_1") (pintype "passive"))
      (node (ref "U4") (pin "41") (pinfunction "CLK125_NDO/LED_MODE_41") (pintype "bidirectional"))
    )
    (net (code "11") (name "Net-(U4A-GTX_CLK)") (class "Default")
      (node (ref "R14") (pin "2") (pinfunction "2_2") (pintype "passive"))
      (node (ref "U4") (pin "24") (pinfunction "GTX_CLK_24") (pintype "input"))
    )
    (net (code "12") (name "Net-(U4A-INT_N{slash}PME_N2)") (class "Default")
      (node (ref "R85") (pin "1") (pinfunction "1_1") (pintype "passive"))
      (node (ref "R87") (pin "1") (pinfunction "1_1") (pintype "passive"))
      (node (ref "U4") (pin "38") (pinfunction "INT_N/PME_N2_38") (pintype "output"))
    )
    (net (code "13") (name "Net-(U4A-ISET)") (class "Default")
      (node (ref "R89") (pin "2") (pinfunction "2_2") (pintype "passive"))
      (node (ref "U4") (pin "48") (pinfunction "ISET_48") (pintype "input"))
    )
    (net (code "14") (name "Net-(U4A-LED1{slash}PHYAD0{slash}PME_N1)") (class "Default")
      (node (ref "R95") (pin "1") (pinfunction "1_1") (pintype "passive"))
      (node (ref "U4") (pin "17") (pinfunction "LED1/PHYAD0/PME_N1_17") (pintype "bidirectional"))
    )
    (net (code "15") (name "Net-(U4A-LED2{slash}PHYAD1)") (class "Default")
      (node (ref "R96") (pin "1") (pinfunction "1_1") (pintype "passive"))
      (node (ref "U4") (pin "15") (pinfunction "LED2/PHYAD1_15") (pintype "bidirectional"))
    )
    (net (code "16") (name "Net-(U4A-MDC)") (class "Default")
      (node (ref "R84") (pin "2") (pinfunction "2_2") (pintype "passive"))
      (node (ref "U4") (pin "36") (pinfunction "MDC_36") (pintype "input"))
    )
    (net (code "17") (name "Net-(U4A-MDIO)") (class "Default")
      (node (ref "R86") (pin "2") (pinfunction "2_2") (pintype "passive"))
      (node (ref "R88") (pin "2") (pinfunction "2_2") (pintype "passive"))
      (node (ref "U4") (pin "37") (pinfunction "MDIO_37") (pintype "bidirectional"))
    )
    (net (code "18") (name "Net-(U4A-RESET_N)") (class "Default")
      (node (ref "R83") (pin "1") (pinfunction "1_1") (pintype "passive"))
      (node (ref "U4") (pin "42") (pinfunction "RESET_N_42") (pintype "input"))
    )
    (net (code "19") (name "Net-(U4A-RXD0{slash}MODE0)") (class "Default")
      (node (ref "R22") (pin "2") (pinfunction "2_2") (pintype "passive"))
      (node (ref "U4") (pin "32") (pinfunction "RXD0/MODE0_32") (pintype "bidirectional"))
    )
    (net (code "20") (name "Net-(U4A-RXD1{slash}MODE1)") (class "Default")
      (node (ref "R23") (pin "2") (pinfunction "2_2") (pintype "passive"))
      (node (ref "U4") (pin "31") (pinfunction "RXD1/MODE1_31") (pintype "bidirectional"))
    )
    (net (code "21") (name "Net-(U4A-RXD2{slash}MODE2)") (class "Default")
      (node (ref "R24") (pin "2") (pinfunction "2_2") (pintype "passive"))
      (node (ref "U4") (pin "28") (pinfunction "RXD2/MODE2_28") (pintype "bidirectional"))
    )
    (net (code "22") (name "Net-(U4A-RXD3{slash}MODE3)") (class "Default")
      (node (ref "R25") (pin "2") (pinfunction "2_2") (pintype "passive"))
      (node (ref "U4") (pin "27") (pinfunction "RXD3/MODE3_27") (pintype "bidirectional"))
    )
    (net (code "23") (name "Net-(U4A-RX_CLK{slash}PHYAD2)") (class "Default")
      (node (ref "R20") (pin "2") (pinfunction "2_2") (pintype "passive"))
      (node (ref "U4") (pin "35") (pinfunction "RX_CLK/PHYAD2_35") (pintype "bidirectional"))
    )
    (net (code "24") (name "Net-(U4A-RX_DV{slash}CLK125_EN)") (class "Default")
      (node (ref "R21") (pin "2") (pinfunction "2_2") (pintype "passive"))
      (node (ref "U4") (pin "33") (pinfunction "RX_DV/CLK125_EN_33") (pintype "bidirectional"))
    )
    (net (code "25") (name "Net-(U4A-TXD0)") (class "Default")
      (node (ref "R16") (pin "2") (pinfunction "2_2") (pintype "passive"))
      (node (ref "U4") (pin "19") (pinfunction "TXD0_19") (pintype "input"))
    )
    (net (code "26") (name "Net-(U4A-TXD1)") (class "Default")
      (node (ref "R17") (pin "2") (pinfunction "2_2") (pintype "passive"))
      (node (ref "U4") (pin "20") (pinfunction "TXD1_20") (pintype "input"))
    )
    (net (code "27") (name "Net-(U4A-TXD2)") (class "Default")
      (node (ref "R18") (pin "2") (pinfunction "2_2") (pintype "passive"))
      (node (ref "U4") (pin "21") (pinfunction "TXD2_21") (pintype "input"))
    )
    (net (code "28") (name "Net-(U4A-TXD3)") (class "Default")
      (node (ref "R19") (pin "2") (pinfunction "2_2") (pintype "passive"))
      (node (ref "U4") (pin "22") (pinfunction "TXD3_22") (pintype "input"))
    )
    (net (code "29") (name "Net-(U4A-TX_EN)") (class "Default")
      (node (ref "R15") (pin "2") (pinfunction "2_2") (pintype "passive"))
      (node (ref "U4") (pin "25") (pinfunction "TX_EN_25") (pintype "input"))
    )
    (net (code "30") (name "P1V2") (class "Default")
      (node (ref "C63") (pin "1") (pinfunction "1_1") (pintype "passive"))
      (node (ref "C64") (pin "2") (pinfunction "2_2") (pintype "passive"))
      (node (ref "C65") (pin "1") (pinfunction "1_1") (pintype "passive"))
      (node (ref "C78") (pin "1") (pinfunction "1_1") (pintype "passive"))
      (node (ref "C79") (pin "2") (pinfunction "2_2") (pintype "passive"))
      (node (ref "C80") (pin "1") (pinfunction "1_1") (pintype "passive"))
      (node (ref "C90") (pin "1") (pinfunction "1_1") (pintype "passive"))
      (node (ref "C91") (pin "2") (pinfunction "2_2") (pintype "passive"))
      (node (ref "C92") (pin "1") (pinfunction "1_1") (pintype "passive"))
      (node (ref "FB5") (pin "1") (pinfunction "1_1") (pintype "passive"))
      (node (ref "FB6") (pin "1") (pinfunction "1_1") (pintype "passive"))
      (node (ref "R92") (pin "1") (pinfunction "1_1") (pintype "passive"))
    )
    (net (code "31") (name "P3V3") (class "Default")
      (node (ref "C100") (pin "1") (pinfunction "1_1") (pintype "passive"))
      (node (ref "C70") (pin "1") (pinfunction "1_1") (pintype "passive"))
      (node (ref "C71") (pin "2") (pinfunction "2_2") (pintype "passive"))
      (node (ref "C72") (pin "1") (pinfunction "1_1") (pintype "passive"))
      (node (ref "C98") (pin "1") (pinfunction "1_1") (pintype "passive"))
      (node (ref "C99") (pin "2") (pinfunction "2_2") (pintype "passive"))
      (node (ref "FB7") (pin "1") (pinfunction "1_1") (pintype "passive"))
      (node (ref "R85") (pin "2") (pinfunction "2_2") (pintype "passive"))
      (node (ref "R88") (pin "1") (pinfunction "1_1") (pintype "passive"))
      (node (ref "R90") (pin "2") (pinfunction "2_2") (pintype "passive"))
      (node (ref "R91") (pin "1") (pinfunction "1_1") (pintype "passive"))
    )
    (net (code "32") (name "P6_LED0") (class "Default")
      (node (ref "R95") (pin "2") (pinfunction "2_2") (pintype "passive"))
    )
    (net (code "33") (name "P6_LED1") (class "Default")
      (node (ref "R96") (pin "2") (pinfunction "2_2") (pintype "passive"))
    )
    (net (code "34") (name "P6_RGMII_RXCLK") (class "Default")
      (node (ref "R14") (pin "1") (pinfunction "1_1") (pintype "passive"))
    )
    (net (code "35") (name "P6_RGMII_RXCTL") (class "Default")
      (node (ref "R15") (pin "1") (pinfunction "1_1") (pintype "passive"))
    )
    (net (code "36") (name "P6_RGMII_RXD0") (class "Default")
      (node (ref "R16") (pin "1") (pinfunction "1_1") (pintype "passive"))
    )
    (net (code "37") (name "P6_RGMII_RXD1") (class "Default")
      (node (ref "R17") (pin "1") (pinfunction "1_1") (pintype "passive"))
    )
    (net (code "38") (name "P6_RGMII_RXD2") (class "Default")
      (node (ref "R18") (pin "1") (pinfunction "1_1") (pintype "passive"))
    )
    (net (code "39") (name "P6_RGMII_RXD3") (class "Default")
      (node (ref "R19") (pin "1") (pinfunction "1_1") (pintype "passive"))
    )
    (net (code "40") (name "P6_RGMII_TXCLK") (class "Default")
      (node (ref "R20") (pin "1") (pinfunction "1_1") (pintype "passive"))
    )
    (net (code "41") (name "P6_RGMII_TXCTL") (class "Default")
      (node (ref "R21") (pin "1") (pinfunction "1_1") (pintype "passive"))
    )
    (net (code "42") (name "P6_RGMII_TXD0") (class "Default")
      (node (ref "R22") (pin "1") (pinfunction "1_1") (pintype "passive"))
    )
    (net (code "43") (name "P6_RGMII_TXD1") (class "Default")
      (node (ref "R23") (pin "1") (pinfunction "1_1") (pintype "passive"))
    )
    (net (code "44") (name "P6_RGMII_TXD2") (class "Default")
      (node (ref "R24") (pin "1") (pinfunction "1_1") (pintype "passive"))
    )
    (net (code "45") (name "P6_RGMII_TXD3") (class "Default")
      (node (ref "R25") (pin "1") (pinfunction "1_1") (pintype "passive"))
    )
    (net (code "46") (name "PHY_25MHz") (class "Default")
      (node (ref "U4") (pin "46") (pinfunction "XI_46") (pintype "input"))
    )
    (net (code "47") (name "PHY_AVDDH") (class "Default")
      (node (ref "C101") (pin "1") (pinfunction "1_1") (pintype "passive"))
      (node (ref "C102") (pin "2") (pinfunction "2_2") (pintype "passive"))
      (node (ref "C103") (pin "1") (pinfunction "1_1") (pintype "passive"))
      (node (ref "C104") (pin "1") (pinfunction "1_1") (pintype "passive"))
      (node (ref "C105") (pin "1") (pinfunction "1_1") (pintype "passive"))
      (node (ref "FB7") (pin "2") (pinfunction "2_2") (pintype "passive"))
      (node (ref "U4") (pin "1") (pinfunction "AVDDH_1") (pintype "power_in"))
      (node (ref "U4") (pin "12") (pinfunction "AVDDH_12") (pintype "power_in"))
    )
    (net (code "48") (name "PHY_AVDDL") (class "Default")
      (node (ref "C93") (pin "1") (pinfunction "1_1") (pintype "passive"))
      (node (ref "C94") (pin "2") (pinfunction "2_2") (pintype "passive"))
      (node (ref "C95") (pin "1") (pinfunction "1_1") (pintype "passive"))
      (node (ref "C96") (pin "1") (pinfunction "1_1") (pintype "passive"))
      (node (ref "C97") (pin "1") (pinfunction "1_1") (pintype "passive"))
      (node (ref "FB6") (pin "2") (pinfunction "2_2") (pintype "passive"))
      (node (ref "U4") (pin "4") (pinfunction "AVDDL_4") (pintype "power_in"))
      (node (ref "U4") (pin "9") (pinfunction "AVDDL_9") (pintype "power_in"))
    )
    (net (code "49") (name "PHY_AVDDL_PLL") (class "Default")
      (node (ref "C66") (pin "1") (pinfunction "1_1") (pintype "passive"))
      (node (ref "C67") (pin "2") (pinfunction "2_2") (pintype "passive"))
      (node (ref "C68") (pin "1") (pinfunction "1_1") (pintype "passive"))
      (node (ref "C69") (pin "1") (pinfunction "1_1") (pintype "passive"))
      (node (ref "FB5") (pin "2") (pinfunction "2_2") (pintype "passive"))
      (node (ref "U4") (pin "44") (pinfunction "AVDDL_PLL_44") (pintype "power_in"))
    )
    (net (code "50") (name "PHY_DVDDH") (class "Default")
      (node (ref "C182") (pin "1") (pinfunction "1_1") (pintype "passive"))
      (node (ref "C73") (pin "1") (pinfunction "1_1") (pintype "passive"))
      (node (ref "C74") (pin "2") (pinfunction "2_2") (pintype "passive"))
      (node (ref "C75") (pin "1") (pinfunction "1_1") (pintype "passive"))
      (node (ref "C76") (pin "1") (pinfunction "1_1") (pintype "passive"))
      (node (ref "C77") (pin "1") (pinfunction "1_1") (pintype "passive"))
      (node (ref "R91") (pin "2") (pinfunction "2_2") (pintype "passive"))
      (node (ref "U4") (pin "16") (pinfunction "DVDDH_16") (pintype "power_in"))
      (node (ref "U4") (pin "34") (pinfunction "DVDDH_34") (pintype "power_in"))
      (node (ref "U4") (pin "40") (pinfunction "DVDDH_40") (pintype "power_in"))
    )
    (net (code "51") (name "PHY_DVDDL") (class "Default")
      (node (ref "C81") (pin "1") (pinfunction "1_1") (pintype "passive"))
      (node (ref "C82") (pin "2") (pinfunction "2_2") (pintype "passive"))
      (node (ref "C83") (pin "1") (pinfunction "1_1") (pintype "passive"))
      (node (ref "C84") (pin "1") (pinfunction "1_1") (pintype "passive"))
      (node (ref "C85") (pin "1") (pinfunction "1_1") (pintype "passive"))
      (node (ref "C86") (pin "1") (pinfunction "1_1") (pintype "passive"))
      (node (ref "C87") (pin "1") (pinfunction "1_1") (pintype "passive"))
      (node (ref "C88") (pin "1") (pinfunction "1_1") (pintype "passive"))
      (node (ref "C89") (pin "1") (pinfunction "1_1") (pintype "passive"))
      (node (ref "R92") (pin "2") (pinfunction "2_2") (pintype "passive"))
      (node (ref "U4") (pin "14") (pinfunction "DVDDL_14") (pintype "power_in"))
      (node (ref "U4") (pin "18") (pinfunction "DVDDL_18") (pintype "power_in"))
      (node (ref "U4") (pin "23") (pinfunction "DVDDL_23") (pintype "power_in"))
      (node (ref "U4") (pin "26") (pinfunction "DVDDL_26") (pintype "power_in"))
      (node (ref "U4") (pin "30") (pinfunction "DVDDL_30") (pintype "power_in"))
      (node (ref "U4") (pin "39") (pinfunction "DVDDL_39") (pintype "power_in"))
    )
    (net (code "52") (name "PHY_INT_N") (class "Default")
      (node (ref "R87") (pin "2") (pinfunction "2_2") (pintype "passive"))
    )
    (net (code "53") (name "PHY_MDC") (class "Default")
      (node (ref "R84") (pin "1") (pinfunction "1_1") (pintype "passive"))
    )
    (net (code "54") (name "PHY_MDIO") (class "Default")
      (node (ref "R86") (pin "1") (pinfunction "1_1") (pintype "passive"))
    )
    (net (code "55") (name "PHY_RST_N") (class "Default")
      (node (ref "R83") (pin "2") (pinfunction "2_2") (pintype "passive"))
    )
    (net (code "56") (name "unconnected-(U4A-LDO_O-Pad43)") (class "Default")
      (node (ref "U4") (pin "43") (pinfunction "LDO_O_43") (pintype "output"))
    )
    (net (code "57") (name "unconnected-(U4A-XO-Pad45)") (class "Default")
      (node (ref "U4") (pin "45") (pinfunction "XO_45") (pintype "passive"))
    )
    (net (code "58") (name "unconnected-(U4B-NC-Pad13)") (class "Default")
      (node (ref "U4") (pin "13") (pinfunction "NC_13") (pintype "passive"))
    )
    (net (code "59") (name "unconnected-(U4B-NC-Pad47)") (class "Default")
      (node (ref "U4") (pin "47") (pinfunction "NC_47") (pintype "passive"))
    )
  )
)
